# SOURCE.net
KiCad netlist of a schematic drawn in Altium Designer
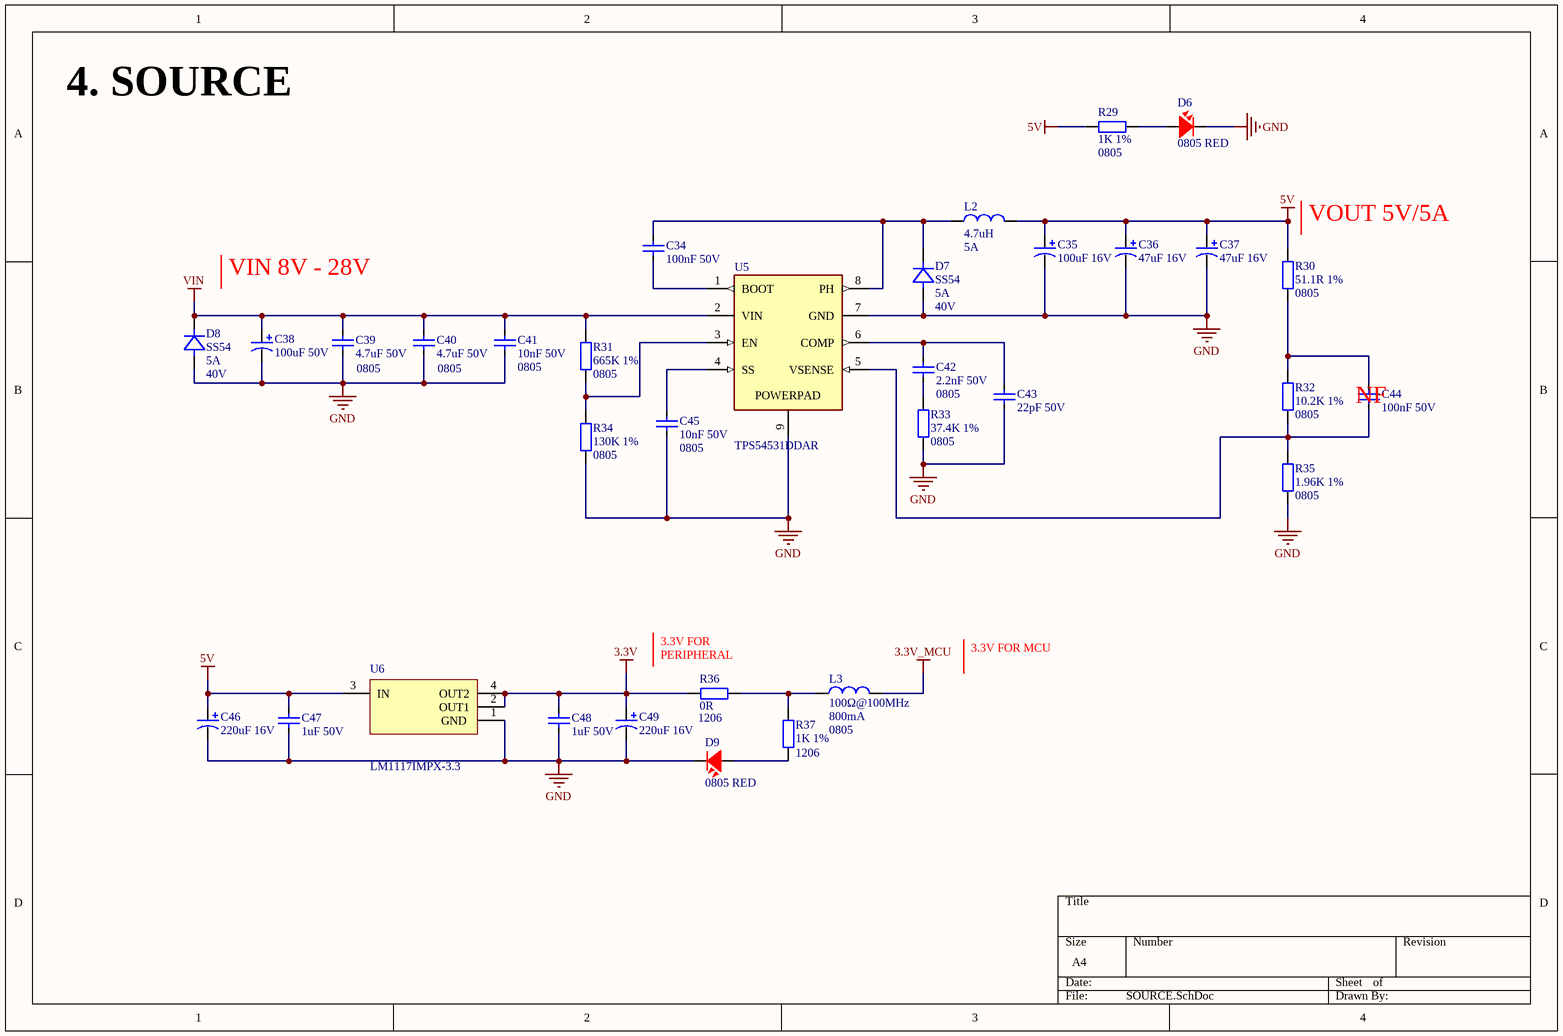
[diagram p0: SOURCE.SchDoc]

(export (version "E")
  (design (tool "Eeschema 10.0.6"))
  (components
    (comp (ref "C34")
      (value "100nF 50V")
      (footprint "CAP_SMD_0805")
      (description "0.1 µF ±10% 50V Ceramic Capacitor X7R 0805 (2012 Metric)")
      (fields
        (field (name "MANUFACTURER") "YAGEO")
        (field (name "MANUFACTURE PART NUMBER") "CC0805KRX7R9BB104")
      )
      (libsource (lib "Capacitors") (part "C0805_MLCC_100nF_50V"))
    )
    (comp (ref "C35")
      (value "100uF 16V")
      (footprint "CAP-ALU-SMD-D")
      (description "100uF 16V 63mA@120Hz ±20% SMD,D6.3xL5.4mm Aluminum Electrolytic Capacitors - SMD ROHS")
      (fields
        (field (name "MANUFACTURER") "DMBJ")
        (field (name "MANUFACTURE PART NUMBER") "RVT1C101M0605 100UF 16V")
      )
      (libsource (lib "Capacitors") (part "C_ALU_100uF_16V"))
    )
    (comp (ref "C36")
      (value "47uF 16V")
      (footprint "CAP-ALU-SMD-C")
      (description "47uF 16V 33mA@120Hz ±20% SMD,D5xL5.4mm Aluminum Electrolytic Capacitors - SMD ROHS")
      (fields
        (field (name "MANUFACTURER") "DMBJ")
        (field (name "MANUFACTURE PART NUMBER") "RVT1C470M0505 47UF 16V")
      )
      (libsource (lib "Capacitors") (part "C_ALU_47uF_16V"))
    )
    (comp (ref "C37")
      (value "47uF 16V")
      (footprint "CAP-ALU-SMD-C")
      (description "47uF 16V 33mA@120Hz ±20% SMD,D5xL5.4mm Aluminum Electrolytic Capacitors - SMD ROHS")
      (fields
        (field (name "MANUFACTURER") "DMBJ")
        (field (name "MANUFACTURE PART NUMBER") "RVT1C470M0505 47UF 16V")
      )
      (libsource (lib "Capacitors") (part "C_ALU_47uF_16V"))
    )
    (comp (ref "C38")
      (value "100uF 50V")
      (footprint "CAP-ALU-SMD-F")
      (description "100uF 50V 140mA@120Hz ±20% SMD,D8xL10mm Aluminum Electrolytic Capacitors - SMD ROHS")
      (fields
        (field (name "MANUFACTURER") "Nichicon")
        (field (name "MANUFACTURE PART NUMBER") "UWT1H101MNL1GS")
      )
      (libsource (lib "Capacitors") (part "C_ALU_100uF_50V"))
    )
    (comp (ref "C39")
      (value "4.7uF 50V")
      (footprint "CAP_SMD_0805")
      (description "4.7 µF ±10% 50V Ceramic Capacitor X5R 0805 (2012 Metric)")
      (fields
        (field (name "MANUFACTURER") "Samsung Electro-Mechanics")
        (field (name "MANUFACTURE PART NUMBER") "CL21A475KBQNNNE")
        (field (name "SIZE") "0805")
      )
      (libsource (lib "Capacitors") (part "C0805_MLCC_4.7uF_50V"))
    )
    (comp (ref "C40")
      (value "4.7uF 50V")
      (footprint "CAP_SMD_0805")
      (description "4.7 µF ±10% 50V Ceramic Capacitor X5R 0805 (2012 Metric)")
      (fields
        (field (name "MANUFACTURER") "Samsung Electro-Mechanics")
        (field (name "MANUFACTURE PART NUMBER") "CL21A475KBQNNNE")
        (field (name "SIZE") "0805")
      )
      (libsource (lib "Capacitors") (part "C0805_MLCC_4.7uF_50V"))
    )
    (comp (ref "C41")
      (value "10nF 50V")
      (footprint "CAP_SMD_0805")
      (description "10000 pF ±10% 50V Ceramic Capacitor X7R 0805 (2012 Metric)")
      (fields
        (field (name "MANUFACTURER") "Samsung Electro-Mechanics")
        (field (name "MANUFACTURE PART NUMBER") "CL21B103KBANNNC")
        (field (name "SIZE") "0805")
      )
      (libsource (lib "Capacitors") (part "C0805_MLCC_10nF_50V"))
    )
    (comp (ref "C42")
      (value "2.2nF 50V")
      (footprint "CAP_SMD_0805")
      (description "2200 pF ±1% 50V Ceramic Capacitor C0G, NP0 0805 (2012 Metric)")
      (fields
        (field (name "MANUFACTURER") "YAGEO")
        (field (name "MANUFACTURE PART NUMBER") "CC0805FKNPO9BN222")
        (field (name "SIZE") "0805")
      )
      (libsource (lib "Capacitors") (part "C0805_MLCC_2.2nF_50V"))
    )
    (comp (ref "C43")
      (value "22pF 50V")
      (footprint "CAP_SMD_0805")
      (description "22 pF ±1% 250V Ceramic Capacitor C0G, NP0 0805 (2012 Metric)")
      (fields
        (field (name "MANUFACTURER") "KYOCERA AVX")
        (field (name "MANUFACTURE PART NUMBER") "600F220FT250XT")
      )
      (libsource (lib "Capacitors") (part "C0805_MLCC_22pF_50V"))
    )
    (comp (ref "C44")
      (value "100nF 50V")
      (footprint "CAP_SMD_0805")
      (description "0.1 µF ±10% 50V Ceramic Capacitor X7R 0805 (2012 Metric)")
      (fields
        (field (name "MANUFACTURER") "YAGEO")
        (field (name "MANUFACTURE PART NUMBER") "CC0805KRX7R9BB104")
      )
      (libsource (lib "Capacitors") (part "C0805_MLCC_100nF_50V"))
    )
    (comp (ref "C45")
      (value "10nF 50V")
      (footprint "CAP_SMD_0805")
      (description "10000 pF ±10% 50V Ceramic Capacitor X7R 0805 (2012 Metric)")
      (fields
        (field (name "MANUFACTURER") "Samsung Electro-Mechanics")
        (field (name "MANUFACTURE PART NUMBER") "CL21B103KBANNNC")
        (field (name "SIZE") "0805")
      )
      (libsource (lib "Capacitors") (part "C0805_MLCC_10nF_50V"))
    )
    (comp (ref "C46")
      (value "220uF 16V")
      (footprint "CAP-ALU-SMD-D")
      (description "16V 220uF ±20% SMD,6.3x7.7mm Solid Capacitors ROHS")
      (fields
        (field (name "MANUFACTURER") "Lelon")
        (field (name "MANUFACTURE PART NUMBER") "OVZ221M1CTR-0608ACS")
      )
      (libsource (lib "Capacitors") (part "C_ALU_220uF_16V"))
    )
    (comp (ref "C47")
      (value "1uF 50V")
      (footprint "CAP_SMD_0805")
      (description "1 µF ±10% 50V Ceramic Capacitor X7R 0805 (2012 Metric)")
      (fields
        (field (name "MANUFACTURER") "Samsung Electro-Mechanics")
        (field (name "MANUFACTURE PART NUMBER") "CL21B105KBFNNNG")
      )
      (libsource (lib "Capacitors") (part "C0805_MLCC_1uF_50V"))
    )
    (comp (ref "C48")
      (value "1uF 50V")
      (footprint "CAP_SMD_0805")
      (description "1 µF ±10% 50V Ceramic Capacitor X7R 0805 (2012 Metric)")
      (fields
        (field (name "MANUFACTURER") "Samsung Electro-Mechanics")
        (field (name "MANUFACTURE PART NUMBER") "CL21B105KBFNNNG")
      )
      (libsource (lib "Capacitors") (part "C0805_MLCC_1uF_50V"))
    )
    (comp (ref "C49")
      (value "220uF 16V")
      (footprint "CAP-ALU-SMD-D")
      (description "16V 220uF ±20% SMD,6.3x7.7mm Solid Capacitors ROHS")
      (fields
        (field (name "MANUFACTURER") "Lelon")
        (field (name "MANUFACTURE PART NUMBER") "OVZ221M1CTR-0608ACS")
      )
      (libsource (lib "Capacitors") (part "C_ALU_220uF_16V"))
    )
    (comp (ref "D6")
      (value "0805 RED")
      (footprint "LED-0805-Red")
      (description "Red 625nm LED Indication - Discrete 2V 0805 (2012 Metric)")
      (fields
        (field (name "MANUFACTURER") "Würth Elektronik")
        (field (name "MANUFACTURE PART NUMBER") "150080RS75000")
      )
      (libsource (lib "LEDs") (part "LED_0805_RED"))
    )
    (comp (ref "D7")
      (value "SS54")
      (footprint "SMA")
      (description "DIODE SCHOTTKY 40V 5A SMA")
      (fields
        (field (name "MANUFACTURER") "EVVO")
        (field (name "CURRENT") "5A")
        (field (name "DC VOLTAGE") "40V")
      )
      (libsource (lib "Diode") (part "SS54"))
    )
    (comp (ref "D8")
      (value "SS54")
      (footprint "SMA")
      (description "DIODE SCHOTTKY 40V 5A SMA")
      (fields
        (field (name "MANUFACTURER") "EVVO")
        (field (name "CURRENT") "5A")
        (field (name "DC VOLTAGE") "40V")
      )
      (libsource (lib "Diode") (part "SS54"))
    )
    (comp (ref "D9")
      (value "0805 RED")
      (footprint "LED-0805-Red")
      (description "Red 625nm LED Indication - Discrete 2V 0805 (2012 Metric)")
      (fields
        (field (name "MANUFACTURER") "Würth Elektronik")
        (field (name "MANUFACTURE PART NUMBER") "150080RS75000")
      )
      (libsource (lib "LEDs") (part "LED_0805_RED"))
    )
    (comp (ref "L2")
      (value "4.7uH 5A")
      (footprint "L0630")
      (description "4.7 µH Shielded Molded Inductor 3.2 A 81.3mOhm Max Nonstandard")
      (fields
        (field (name "MANUFACTURER") "SHOU HAN")
        (field (name "MANUFACTURE PART NUMBER") "CYA0630-4.7UH")
        (field (name "INDUCTOR") "4.7uH")
        (field (name "CURRENT") "5A")
      )
      (libsource (lib "Inductors") (part "L0630_4.7uH _5A"))
    )
    (comp (ref "L3")
      (value "100Ohms 100Mhz")
      (footprint "FB_0805")
      (fields
        (field (name "MANUFACTURER") "TAI-TECH")
        (field (name "MANUFACTURE PART NUMBER") "FCM2012KF-101T08")
        (field (name "IMPEDANCE @ FREQUENCY") "100Ω@100MHz")
        (field (name "CURRENT") "800mA")
        (field (name "SIZE") "0805")
      )
      (libsource (lib "Inductors") (part "FR_100Ohms_100Mhz"))
    )
    (comp (ref "R29")
      (value "1K 1%")
      (footprint "RES_SMD_0805")
      (description "1 kOhms ±1% 0.125W, 1/8W Chip Resistor 0805 (2012 Metric) Moisture Resistant Thick Film")
      (fields
        (field (name "MANUFACTURER") "YAGEO")
        (field (name "MANUFACTURE PART NUMBER") "311-1.00KCRCT-ND")
        (field (name "SIZE") "0805")
      )
      (libsource (lib "Resistors") (part "R0805_1K"))
    )
    (comp (ref "R30")
      (value "51.1R 1%")
      (footprint "RES_SMD_0805")
      (description "51.1 Ohms ±1% 0.125W, 1/8W Chip Resistor 0805 (2012 Metric) Moisture Resistant Thick Film")
      (fields
        (field (name "MANUFACTURER") "YAGEO")
        (field (name "MANUFACTURE PART NUMBER") "RC0805FR-0751R1L")
        (field (name "SIZE") "0805")
      )
      (libsource (lib "Resistors") (part "R0805_51.1R"))
    )
    (comp (ref "R31")
      (value "665K 1%")
      (footprint "RES_SMD_0805")
      (description "665 kOhms ±1% 0.125W, 1/8W Chip Resistor 0805 (2012 Metric) Moisture Resistant Thick Film")
      (fields
        (field (name "MANUFACTURER") "YAGEO")
        (field (name "MANUFACTURE PART NUMBER") "RC0805FR-07665KL")
        (field (name "SIZE") "0805")
      )
      (libsource (lib "Resistors") (part "R0805_665K"))
    )
    (comp (ref "R32")
      (value "10.2K 1%")
      (footprint "RES_SMD_0805")
      (description "10.2 kOhms ±1% 0.125W, 1/8W Chip Resistor 0805 (2012 Metric) Moisture Resistant Thick Film")
      (fields
        (field (name "MANUFACTURER") "YAGEO")
        (field (name "MANUFACTURE PART NUMBER") "RC0805FR-0710K2L")
        (field (name "SIZE") "0805")
      )
      (libsource (lib "Resistors") (part "R0805_10.2K"))
    )
    (comp (ref "R33")
      (value "37.4K 1%")
      (footprint "RES_SMD_0805")
      (description "37.4 kOhms ±1% 0.125W, 1/8W Chip Resistor 0805 (2012 Metric) Moisture Resistant Thick Film")
      (fields
        (field (name "MANUFACTURER") "YAGEO")
        (field (name "MANUFACTURE PART NUMBER") "RC0805FR-0737K4L")
        (field (name "SIZE") "0805")
      )
      (libsource (lib "Resistors") (part "R0805_37.4K"))
    )
    (comp (ref "R34")
      (value "130K 1%")
      (footprint "RES_SMD_0805")
      (description "130 kOhms ±1% 0.125W, 1/8W Chip Resistor 0805 (2012 Metric) Moisture Resistant Thick Film")
      (fields
        (field (name "MANUFACTURER") "YAGEO")
        (field (name "MANUFACTURE PART NUMBER") "RC0805FR-07130KL")
        (field (name "SIZE") "0805")
      )
      (libsource (lib "Resistors") (part "R0805_130K"))
    )
    (comp (ref "R35")
      (value "1.96K 1%")
      (footprint "RES_SMD_0805")
      (description "1.96 kOhms ±1% 0.125W, 1/8W Chip Resistor 0805 (2012 Metric) Moisture Resistant Thick Film")
      (fields
        (field (name "MANUFACTURER") "YAGEO")
        (field (name "MANUFACTURE PART NUMBER") "RC0805FR-071K96L")
        (field (name "SIZE") "0805")
      )
      (libsource (lib "Resistors") (part "R0805_1.96K"))
    )
    (comp (ref "R36")
      (value "0R")
      (footprint "RES_SMD_1206")
      (description "0 Ohms Jumper Chip Resistor 1206 (3216 Metric) Moisture Resistant Thick Film")
      (fields
        (field (name "MANUFACTURER") "YAGEO")
        (field (name "MANUFACTURE PART NUMBER") "RC1206JR-070RL")
        (field (name "SIZE") "1206")
      )
      (libsource (lib "Resistors") (part "R1206_0R"))
    )
    (comp (ref "R37")
      (value "1K 1%")
      (footprint "RES_SMD_1206")
      (description "1 kOhms ±1% 0.5W, 1/2W Chip Resistor 1206 (3216 Metric) Anti-Sulfur Thin Film")
      (fields
        (field (name "MANUFACTURER") "Stackpole Electronics Inc")
        (field (name "MANUFACTURE PART NUMBER") "RNCP1206FTD1K00")
        (field (name "SIZE") "1206")
      )
      (libsource (lib "Resistors") (part "R1206_1K"))
    )
    (comp (ref "U5")
      (value "TPS54531DDAR")
      (footprint "TPS54531DDAR")
      (fields (field (name "MANUFACTURER") "Texas Instruments"))
      (libsource (lib "Voltage_Regulators") (part "TPS54531DDAR"))
    )
    (comp (ref "U6")
      (value "LM1117IMPX-3.3")
      (footprint "SOT-223-4")
      (description "Linear Voltage Regulator IC Positive Fixed 1 Output 800mA SOT-223-4")
      (fields
        (field (name "MANUFACTURER") "Texas Instruments")
        (field (name "MANUFACTURE PART NUMBER") "LM1117IMPX-3.3/NOPB")
      )
      (libsource (lib "Voltage_Regulators") (part "LM1117IMPX-3.3/NOPB"))
    )
  )
  (nets
    (net (code "1") (name "3.3V") (class "Default")
      (node (ref "C48") (pin "2") (pinfunction "2_2") (pintype "passive"))
      (node (ref "C49") (pin "1") (pinfunction "1_1") (pintype "passive"))
      (node (ref "R36") (pin "1") (pinfunction "1_1") (pintype "passive"))
      (node (ref "U6") (pin "2") (pinfunction "OUT1_2") (pintype "passive"))
      (node (ref "U6") (pin "4") (pinfunction "OUT2_4") (pintype "passive"))
    )
    (net (code "2") (name "3.3V_MCU") (class "Default")
      (node (ref "L3") (pin "2") (pinfunction "2_2") (pintype "passive"))
    )
    (net (code "3") (name "5V") (class "Default")
      (node (ref "C35") (pin "1") (pinfunction "1_1") (pintype "passive"))
      (node (ref "C36") (pin "1") (pinfunction "1_1") (pintype "passive"))
      (node (ref "C37") (pin "1") (pinfunction "1_1") (pintype "passive"))
      (node (ref "C46") (pin "1") (pinfunction "1_1") (pintype "passive"))
      (node (ref "C47") (pin "2") (pinfunction "2_2") (pintype "passive"))
      (node (ref "L2") (pin "2") (pinfunction "2_2") (pintype "passive"))
      (node (ref "R29") (pin "1") (pinfunction "1_1") (pintype "passive"))
      (node (ref "R30") (pin "2") (pinfunction "2_2") (pintype "passive"))
      (node (ref "U6") (pin "3") (pinfunction "IN_3") (pintype "passive"))
    )
    (net (code "4") (name "GND") (class "Default")
      (node (ref "C35") (pin "2") (pinfunction "2_2") (pintype "passive"))
      (node (ref "C36") (pin "2") (pinfunction "2_2") (pintype "passive"))
      (node (ref "C37") (pin "2") (pinfunction "2_2") (pintype "passive"))
      (node (ref "C38") (pin "2") (pinfunction "2_2") (pintype "passive"))
      (node (ref "C39") (pin "1") (pinfunction "1_1") (pintype "passive"))
      (node (ref "C40") (pin "1") (pinfunction "1_1") (pintype "passive"))
      (node (ref "C41") (pin "1") (pinfunction "1_1") (pintype "passive"))
      (node (ref "C43") (pin "1") (pinfunction "1_1") (pintype "passive"))
      (node (ref "C45") (pin "1") (pinfunction "1_1") (pintype "passive"))
      (node (ref "C46") (pin "2") (pinfunction "2_2") (pintype "passive"))
      (node (ref "C47") (pin "1") (pinfunction "1_1") (pintype "passive"))
      (node (ref "C48") (pin "1") (pinfunction "1_1") (pintype "passive"))
      (node (ref "C49") (pin "2") (pinfunction "2_2") (pintype "passive"))
      (node (ref "D6") (pin "2") (pinfunction "2_2") (pintype "passive"))
      (node (ref "D7") (pin "A") (pinfunction "A_A") (pintype "passive"))
      (node (ref "D8") (pin "A") (pinfunction "A_A") (pintype "passive"))
      (node (ref "D9") (pin "2") (pinfunction "2_2") (pintype "passive"))
      (node (ref "R33") (pin "1") (pinfunction "1_1") (pintype "passive"))
      (node (ref "R34") (pin "1") (pinfunction "1_1") (pintype "passive"))
      (node (ref "R35") (pin "1") (pinfunction "1_1") (pintype "passive"))
      (node (ref "U5") (pin "7") (pinfunction "GND_7") (pintype "power_in"))
      (node (ref "U5") (pin "9") (pinfunction "POWERPAD_9") (pintype "power_in"))
      (node (ref "U6") (pin "1") (pinfunction "GND_1") (pintype "passive"))
    )
    (net (code "5") (name "Net-(C42-Pad1)") (class "Default")
      (node (ref "C42") (pin "1") (pinfunction "1_1") (pintype "passive"))
      (node (ref "R33") (pin "2") (pinfunction "2_2") (pintype "passive"))
    )
    (net (code "6") (name "Net-(C44-Pad2)") (class "Default")
      (node (ref "C44") (pin "2") (pinfunction "2_2") (pintype "passive"))
      (node (ref "R30") (pin "1") (pinfunction "1_1") (pintype "passive"))
      (node (ref "R32") (pin "2") (pinfunction "2_2") (pintype "passive"))
    )
    (net (code "7") (name "Net-(D6-Pad1)") (class "Default")
      (node (ref "D6") (pin "1") (pinfunction "1_1") (pintype "passive"))
      (node (ref "R29") (pin "2") (pinfunction "2_2") (pintype "passive"))
    )
    (net (code "8") (name "Net-(D9-Pad1)") (class "Default")
      (node (ref "D9") (pin "1") (pinfunction "1_1") (pintype "passive"))
      (node (ref "R37") (pin "1") (pinfunction "1_1") (pintype "passive"))
    )
    (net (code "9") (name "Net-(L3-Pad1)") (class "Default")
      (node (ref "L3") (pin "1") (pinfunction "1_1") (pintype "passive"))
      (node (ref "R36") (pin "2") (pinfunction "2_2") (pintype "passive"))
      (node (ref "R37") (pin "2") (pinfunction "2_2") (pintype "passive"))
    )
    (net (code "10") (name "Net-(U5-BOOT)") (class "Default")
      (node (ref "C34") (pin "1") (pinfunction "1_1") (pintype "passive"))
      (node (ref "U5") (pin "1") (pinfunction "BOOT_1") (pintype "output"))
    )
    (net (code "11") (name "Net-(U5-COMP)") (class "Default")
      (node (ref "C42") (pin "2") (pinfunction "2_2") (pintype "passive"))
      (node (ref "C43") (pin "2") (pinfunction "2_2") (pintype "passive"))
      (node (ref "U5") (pin "6") (pinfunction "COMP_6") (pintype "output"))
    )
    (net (code "12") (name "Net-(U5-EN)") (class "Default")
      (node (ref "R31") (pin "1") (pinfunction "1_1") (pintype "passive"))
      (node (ref "R34") (pin "2") (pinfunction "2_2") (pintype "passive"))
      (node (ref "U5") (pin "3") (pinfunction "EN_3") (pintype "input"))
    )
    (net (code "13") (name "Net-(U5-PH)") (class "Default")
      (node (ref "C34") (pin "2") (pinfunction "2_2") (pintype "passive"))
      (node (ref "D7") (pin "C") (pinfunction "C_C") (pintype "passive"))
      (node (ref "L2") (pin "1") (pinfunction "1_1") (pintype "passive"))
      (node (ref "U5") (pin "8") (pinfunction "PH_8") (pintype "output"))
    )
    (net (code "14") (name "Net-(U5-SS)") (class "Default")
      (node (ref "C45") (pin "2") (pinfunction "2_2") (pintype "passive"))
      (node (ref "U5") (pin "4") (pinfunction "SS_4") (pintype "input"))
    )
    (net (code "15") (name "Net-(U5-VSENSE)") (class "Default")
      (node (ref "C44") (pin "1") (pinfunction "1_1") (pintype "passive"))
      (node (ref "R32") (pin "1") (pinfunction "1_1") (pintype "passive"))
      (node (ref "R35") (pin "2") (pinfunction "2_2") (pintype "passive"))
      (node (ref "U5") (pin "5") (pinfunction "VSENSE_5") (pintype "input"))
    )
    (net (code "16") (name "VIN") (class "Default")
      (node (ref "C38") (pin "1") (pinfunction "1_1") (pintype "passive"))
      (node (ref "C39") (pin "2") (pinfunction "2_2") (pintype "passive"))
      (node (ref "C40") (pin "2") (pinfunction "2_2") (pintype "passive"))
      (node (ref "C41") (pin "2") (pinfunction "2_2") (pintype "passive"))
      (node (ref "D8") (pin "C") (pinfunction "C_C") (pintype "passive"))
      (node (ref "R31") (pin "2") (pinfunction "2_2") (pintype "passive"))
      (node (ref "U5") (pin "2") (pinfunction "VIN_2") (pintype "power_in"))
    )
  )
)
